# summing_amplifier.net
KiCad netlist of a schematic drawn in EAGLE
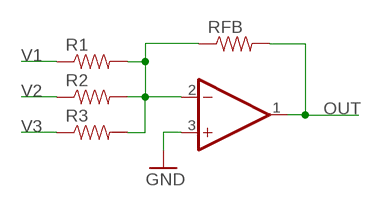
[diagram p0: schematic, sheet 1]

(export (version "E")
  (design (tool "Eeschema 10.0.6"))
  (components
    (comp (ref "IC1")
      (value "MCP6022")
      (footprint "eagle-import:SOIC8_150MIL")
      (libsource (lib "eagle-import") (part "MCP6022"))
    )
    (comp (ref "R1")
      (value "RESISTOR0402-RES")
      (footprint "eagle-import:0402-RES")
      (libsource (lib "eagle-import") (part "RESISTOR0402-RES"))
    )
    (comp (ref "R2")
      (value "RESISTOR0402-RES")
      (footprint "eagle-import:0402-RES")
      (libsource (lib "eagle-import") (part "RESISTOR0402-RES"))
    )
    (comp (ref "R3")
      (value "RESISTOR0402-RES")
      (footprint "eagle-import:0402-RES")
      (libsource (lib "eagle-import") (part "RESISTOR0402-RES"))
    )
    (comp (ref "RFB")
      (value "RESISTOR0402-RES")
      (footprint "eagle-import:0402-RES")
      (libsource (lib "eagle-import") (part "RESISTOR0402-RES"))
    )
  )
  (nets
    (net (code "1") (name "/OUT") (class "Default")
      (node (ref "IC1") (pin "1") (pinfunction "OUT_1") (pintype "output"))
      (node (ref "RFB") (pin "2") (pinfunction "2_2") (pintype "passive"))
    )
    (net (code "2") (name "/V1") (class "Default")
      (node (ref "R1") (pin "1") (pinfunction "1_1") (pintype "passive"))
    )
    (net (code "3") (name "/V2") (class "Default")
      (node (ref "R2") (pin "1") (pinfunction "1_1") (pintype "passive"))
    )
    (net (code "4") (name "/V3") (class "Default")
      (node (ref "R3") (pin "1") (pinfunction "1_1") (pintype "passive"))
    )
    (net (code "5") (name "GND") (class "Default")
      (node (ref "IC1") (pin "3") (pinfunction "+IN_3") (pintype "input"))
    )
    (net (code "6") (name "Net-(IC1A--IN)") (class "Default")
      (node (ref "IC1") (pin "2") (pinfunction "-IN_2") (pintype "input"))
      (node (ref "R1") (pin "2") (pinfunction "2_2") (pintype "passive"))
      (node (ref "R2") (pin "2") (pinfunction "2_2") (pintype "passive"))
      (node (ref "R3") (pin "2") (pinfunction "2_2") (pintype "passive"))
      (node (ref "RFB") (pin "1") (pinfunction "1_1") (pintype "passive"))
    )
  )
)
